# esquema_eletrico.net
KiCad netlist of a schematic drawn in EAGLE
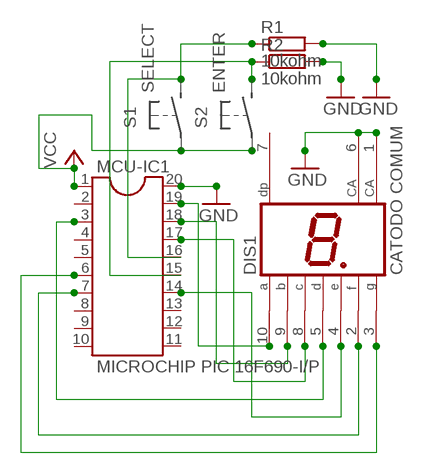
[diagram p0: schematic, sheet 1]

(export (version "E")
  (design (tool "Eeschema 10.0.6"))
  (components
    (comp (ref "DIS1")
      (value "CATODO COMUM")
      (footprint "eagle-import:HDSP-A")
      (libsource (lib "eagle-import") (part "HD-A101"))
    )
    (comp (ref "MCU-IC1")
      (value "MICROCHIP PIC 16F690-I/P")
      (footprint "eagle-import:DIL20")
      (libsource (lib "eagle-import") (part "DIL20"))
    )
    (comp (ref "R1")
      (value "10kohm")
      (footprint "eagle-import:0204V")
      (libsource (lib "eagle-import") (part "R-EU_0204/2V"))
    )
    (comp (ref "R2")
      (value "10kohm")
      (footprint "eagle-import:0204V")
      (libsource (lib "eagle-import") (part "R-EU_0204/2V"))
    )
  )
  (nets
    (net (code "1") (name "GND") (class "Default")
      (node (ref "DIS1") (pin "1") (pinfunction "CA_1") (pintype "passive"))
      (node (ref "DIS1") (pin "6") (pinfunction "CA_6") (pintype "passive"))
      (node (ref "MCU-IC1") (pin "20") (pinfunction "20_20") (pintype "passive"))
      (node (ref "R1") (pin "2") (pinfunction "2_2") (pintype "passive"))
      (node (ref "R2") (pin "2") (pinfunction "2_2") (pintype "passive"))
    )
    (net (code "2") (name "Net-(DIS1-A)") (class "Default")
      (node (ref "DIS1") (pin "10") (pinfunction "A_10") (pintype "passive"))
      (node (ref "MCU-IC1") (pin "19") (pinfunction "19_19") (pintype "passive"))
    )
    (net (code "3") (name "Net-(DIS1-B)") (class "Default")
      (node (ref "DIS1") (pin "9") (pinfunction "B_9") (pintype "passive"))
      (node (ref "MCU-IC1") (pin "18") (pinfunction "18_18") (pintype "passive"))
    )
    (net (code "4") (name "Net-(DIS1-C)") (class "Default")
      (node (ref "DIS1") (pin "8") (pinfunction "C_8") (pintype "passive"))
      (node (ref "MCU-IC1") (pin "17") (pinfunction "17_17") (pintype "passive"))
    )
    (net (code "5") (name "Net-(DIS1-D)") (class "Default")
      (node (ref "DIS1") (pin "5") (pinfunction "D_5") (pintype "passive"))
      (node (ref "MCU-IC1") (pin "3") (pinfunction "3_3") (pintype "passive"))
    )
    (net (code "6") (name "Net-(DIS1-E)") (class "Default")
      (node (ref "DIS1") (pin "4") (pinfunction "E_4") (pintype "passive"))
      (node (ref "MCU-IC1") (pin "14") (pinfunction "14_14") (pintype "passive"))
    )
    (net (code "7") (name "Net-(DIS1-F)") (class "Default")
      (node (ref "DIS1") (pin "2") (pinfunction "F_2") (pintype "passive"))
      (node (ref "MCU-IC1") (pin "7") (pinfunction "7_7") (pintype "passive"))
    )
    (net (code "8") (name "Net-(DIS1-G)") (class "Default")
      (node (ref "DIS1") (pin "3") (pinfunction "G_3") (pintype "passive"))
      (node (ref "MCU-IC1") (pin "6") (pinfunction "6_6") (pintype "passive"))
    )
    (net (code "9") (name "Net-(MCU-IC1-Pad15)") (class "Default")
      (node (ref "MCU-IC1") (pin "15") (pinfunction "15_15") (pintype "passive"))
      (node (ref "R2") (pin "1") (pinfunction "1_1") (pintype "passive"))
    )
    (net (code "10") (name "Net-(MCU-IC1-Pad16)") (class "Default")
      (node (ref "MCU-IC1") (pin "16") (pinfunction "16_16") (pintype "passive"))
      (node (ref "R1") (pin "1") (pinfunction "1_1") (pintype "passive"))
    )
    (net (code "11") (name "VCC") (class "Default")
      (node (ref "MCU-IC1") (pin "1") (pinfunction "1_1") (pintype "passive"))
    )
    (net (code "12") (name "unconnected-(DIS1-DP-Pad7)") (class "Default")
      (node (ref "DIS1") (pin "7") (pinfunction "DP_7") (pintype "passive"))
    )
    (net (code "13") (name "unconnected-(MCU-IC1-Pad2)") (class "Default")
      (node (ref "MCU-IC1") (pin "2") (pinfunction "2_2") (pintype "passive"))
    )
    (net (code "14") (name "unconnected-(MCU-IC1-Pad4)") (class "Default")
      (node (ref "MCU-IC1") (pin "4") (pinfunction "4_4") (pintype "passive"))
    )
    (net (code "15") (name "unconnected-(MCU-IC1-Pad5)") (class "Default")
      (node (ref "MCU-IC1") (pin "5") (pinfunction "5_5") (pintype "passive"))
    )
    (net (code "16") (name "unconnected-(MCU-IC1-Pad8)") (class "Default")
      (node (ref "MCU-IC1") (pin "8") (pinfunction "8_8") (pintype "passive"))
    )
    (net (code "17") (name "unconnected-(MCU-IC1-Pad9)") (class "Default")
      (node (ref "MCU-IC1") (pin "9") (pinfunction "9_9") (pintype "passive"))
    )
    (net (code "18") (name "unconnected-(MCU-IC1-Pad10)") (class "Default")
      (node (ref "MCU-IC1") (pin "10") (pinfunction "10_10") (pintype "passive"))
    )
    (net (code "19") (name "unconnected-(MCU-IC1-Pad11)") (class "Default")
      (node (ref "MCU-IC1") (pin "11") (pinfunction "11_11") (pintype "passive"))
    )
    (net (code "20") (name "unconnected-(MCU-IC1-Pad12)") (class "Default")
      (node (ref "MCU-IC1") (pin "12") (pinfunction "12_12") (pintype "passive"))
    )
    (net (code "21") (name "unconnected-(MCU-IC1-Pad13)") (class "Default")
      (node (ref "MCU-IC1") (pin "13") (pinfunction "13_13") (pintype "passive"))
    )
  )
)
